# ThermoStat2.net
KiCad netlist of a schematic drawn in EAGLE
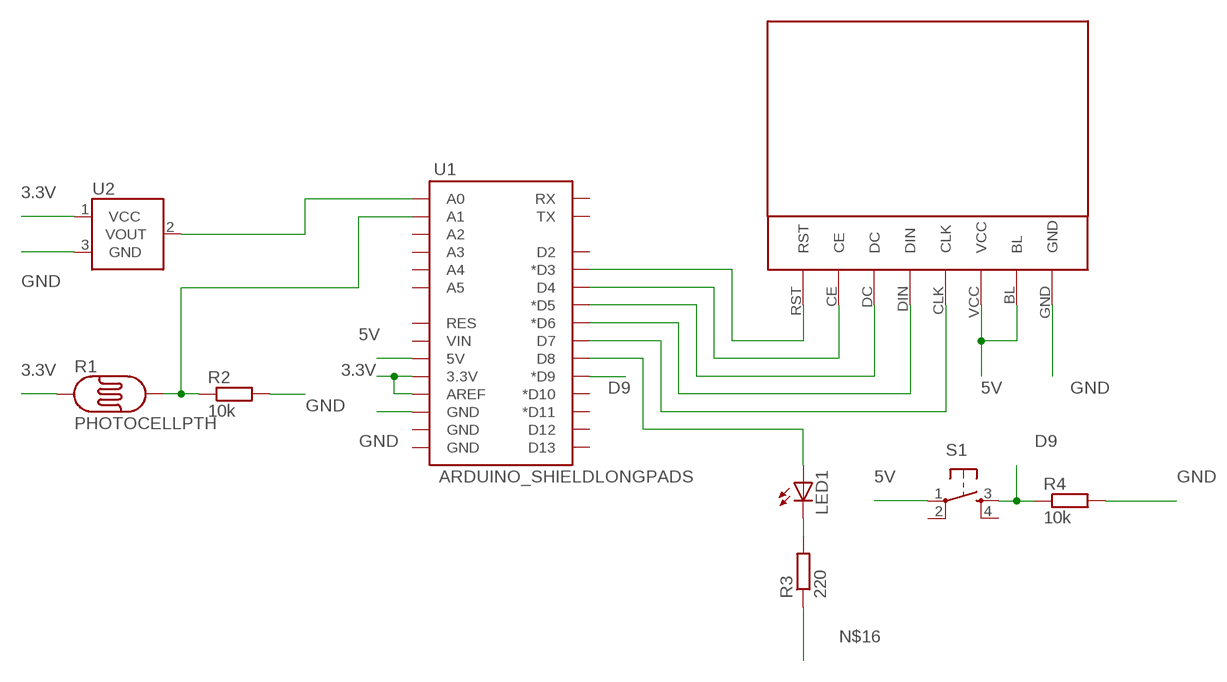
[diagram p0: schematic, sheet 1]

(export (version "E")
  (design (tool "Eeschema 10.0.6"))
  (components
    (comp (ref "LED1")
      (value "LED5MM")
      (footprint "eagle-import:LED5MM")
      (libsource (lib "eagle-import") (part "LED5MM"))
    )
    (comp (ref "R1")
      (value "PHOTOCELLPTH")
      (footprint "eagle-import:PHOTOCELL")
      (libsource (lib "eagle-import") (part "PHOTOCELLPTH"))
    )
    (comp (ref "R2")
      (value "10k")
      (footprint "eagle-import:0207_15")
      (libsource (lib "eagle-import") (part "R-EU_0207/15"))
    )
    (comp (ref "R3")
      (value "220")
      (footprint "eagle-import:0207_15")
      (libsource (lib "eagle-import") (part "R-EU_0207/15"))
    )
    (comp (ref "R4")
      (value "10k")
      (footprint "eagle-import:0207_15")
      (libsource (lib "eagle-import") (part "R-EU_0207/15"))
    )
    (comp (ref "S1")
      (value "TAC_SWITCHPTH")
      (footprint "eagle-import:TACTILE-PTH")
      (libsource (lib "eagle-import") (part "TAC_SWITCHPTH"))
    )
    (comp (ref "U$1")
      (value "NOKIA5510")
      (footprint "eagle-import:NOKIA5510")
      (libsource (lib "eagle-import") (part "NOKIA5510"))
    )
    (comp (ref "U1")
      (value "ARDUINO_SHIELDLONGPADS")
      (footprint "eagle-import:DUEMILANOVE_SHIELD_LONGPADS")
      (libsource (lib "eagle-import") (part "ARDUINO_SHIELDLONGPADS"))
    )
    (comp (ref "U2")
      (value "TMP36GT9")
      (footprint "eagle-import:TO-92")
      (libsource (lib "eagle-import") (part "TMP36GT9"))
    )
  )
  (nets
    (net (code "1") (name "/3.3V") (class "Default")
      (node (ref "R1") (pin "1") (pinfunction "P$1_1") (pintype "bidirectional"))
      (node (ref "U1") (pin "3.3V") (pinfunction "3.3V_3.3V") (pintype "bidirectional"))
      (node (ref "U1") (pin "AREF") (pinfunction "AREF_AREF") (pintype "bidirectional"))
      (node (ref "U2") (pin "1") (pinfunction "VCC_1") (pintype "bidirectional"))
    )
    (net (code "2") (name "/5V") (class "Default")
      (node (ref "S1") (pin "1") (pinfunction "1_1") (pintype "passive"))
      (node (ref "U$1") (pin "BL") (pinfunction "BL_BL") (pintype "bidirectional"))
      (node (ref "U$1") (pin "VCC") (pinfunction "VCC_VCC") (pintype "bidirectional"))
      (node (ref "U1") (pin "5V") (pinfunction "5V_5V") (pintype "bidirectional"))
    )
    (net (code "3") (name "/D9") (class "Default")
      (node (ref "R4") (pin "1") (pinfunction "1_1") (pintype "passive"))
      (node (ref "S1") (pin "3") (pinfunction "3_3") (pintype "passive"))
      (node (ref "U1") (pin "D9") (pinfunction "*D9_D9") (pintype "bidirectional"))
    )
    (net (code "4") (name "/GND") (class "Default")
      (node (ref "R2") (pin "2") (pinfunction "2_2") (pintype "passive"))
      (node (ref "R4") (pin "2") (pinfunction "2_2") (pintype "passive"))
      (node (ref "U$1") (pin "GND") (pinfunction "GND_GND") (pintype "bidirectional"))
      (node (ref "U1") (pin "GND@2") (pinfunction "GND_GND@2") (pintype "bidirectional"))
      (node (ref "U2") (pin "3") (pinfunction "GND_3") (pintype "bidirectional"))
    )
    (net (code "5") (name "/N$16") (class "Default")
      (node (ref "R3") (pin "1") (pinfunction "1_1") (pintype "passive"))
    )
    (net (code "6") (name "Net-(LED1-C)") (class "Default")
      (node (ref "LED1") (pin "K") (pinfunction "C_K") (pintype "passive"))
      (node (ref "R3") (pin "2") (pinfunction "2_2") (pintype "passive"))
    )
    (net (code "7") (name "Net-(LED1-PadA)") (class "Default")
      (node (ref "LED1") (pin "A") (pinfunction "A_A") (pintype "passive"))
      (node (ref "U1") (pin "D8") (pinfunction "D8_D8") (pintype "bidirectional"))
    )
    (net (code "8") (name "Net-(R1-P$2)") (class "Default")
      (node (ref "R1") (pin "2") (pinfunction "P$2_2") (pintype "bidirectional"))
      (node (ref "R2") (pin "1") (pinfunction "1_1") (pintype "passive"))
      (node (ref "U1") (pin "A1") (pinfunction "A1_A1") (pintype "bidirectional"))
    )
    (net (code "9") (name "Net-(U$1-PadCE)") (class "Default")
      (node (ref "U$1") (pin "CE") (pinfunction "CE_CE") (pintype "bidirectional"))
      (node (ref "U1") (pin "D4") (pinfunction "D4_D4") (pintype "bidirectional"))
    )
    (net (code "10") (name "Net-(U$1-PadCLK)") (class "Default")
      (node (ref "U$1") (pin "CLK") (pinfunction "CLK_CLK") (pintype "bidirectional"))
      (node (ref "U1") (pin "D7") (pinfunction "D7_D7") (pintype "bidirectional"))
    )
    (net (code "11") (name "Net-(U1-*D3)") (class "Default")
      (node (ref "U$1") (pin "RST") (pinfunction "RST_RST") (pintype "bidirectional"))
      (node (ref "U1") (pin "D3") (pinfunction "*D3_D3") (pintype "bidirectional"))
    )
    (net (code "12") (name "Net-(U1-*D5)") (class "Default")
      (node (ref "U$1") (pin "DC") (pinfunction "DC_DC") (pintype "bidirectional"))
      (node (ref "U1") (pin "D5") (pinfunction "*D5_D5") (pintype "bidirectional"))
    )
    (net (code "13") (name "Net-(U1-*D6)") (class "Default")
      (node (ref "U$1") (pin "DIN") (pinfunction "DIN_DIN") (pintype "bidirectional"))
      (node (ref "U1") (pin "D6") (pinfunction "*D6_D6") (pintype "bidirectional"))
    )
    (net (code "14") (name "Net-(U2-VOUT)") (class "Default")
      (node (ref "U1") (pin "A0") (pinfunction "A0_A0") (pintype "bidirectional"))
      (node (ref "U2") (pin "2") (pinfunction "VOUT_2") (pintype "bidirectional"))
    )
    (net (code "15") (name "unconnected-(S1-Pad2)") (class "Default")
      (node (ref "S1") (pin "2") (pinfunction "2_2") (pintype "passive"))
    )
    (net (code "16") (name "unconnected-(S1-Pad4)") (class "Default")
      (node (ref "S1") (pin "4") (pinfunction "4_4") (pintype "passive"))
    )
    (net (code "17") (name "unconnected-(U1-*D10-PadD10)") (class "Default")
      (node (ref "U1") (pin "D10") (pinfunction "*D10_D10") (pintype "bidirectional"))
    )
    (net (code "18") (name "unconnected-(U1-*D11-PadD11)") (class "Default")
      (node (ref "U1") (pin "D11") (pinfunction "*D11_D11") (pintype "bidirectional"))
    )
    (net (code "19") (name "unconnected-(U1-GND-PadGND@0)") (class "Default")
      (node (ref "U1") (pin "GND@0") (pinfunction "GND_GND@0") (pintype "bidirectional"))
    )
    (net (code "20") (name "unconnected-(U1-GND-PadGND@1)") (class "Default")
      (node (ref "U1") (pin "GND@1") (pinfunction "GND_GND@1") (pintype "bidirectional"))
    )
    (net (code "21") (name "unconnected-(U1-PadA2)") (class "Default")
      (node (ref "U1") (pin "A2") (pinfunction "A2_A2") (pintype "bidirectional"))
    )
    (net (code "22") (name "unconnected-(U1-PadA3)") (class "Default")
      (node (ref "U1") (pin "A3") (pinfunction "A3_A3") (pintype "bidirectional"))
    )
    (net (code "23") (name "unconnected-(U1-PadA4)") (class "Default")
      (node (ref "U1") (pin "A4") (pinfunction "A4_A4") (pintype "bidirectional"))
    )
    (net (code "24") (name "unconnected-(U1-PadA5)") (class "Default")
      (node (ref "U1") (pin "A5") (pinfunction "A5_A5") (pintype "bidirectional"))
    )
    (net (code "25") (name "unconnected-(U1-PadD2)") (class "Default")
      (node (ref "U1") (pin "D2") (pinfunction "D2_D2") (pintype "bidirectional"))
    )
    (net (code "26") (name "unconnected-(U1-PadD12)") (class "Default")
      (node (ref "U1") (pin "D12") (pinfunction "D12_D12") (pintype "bidirectional"))
    )
    (net (code "27") (name "unconnected-(U1-PadD13)") (class "Default")
      (node (ref "U1") (pin "D13") (pinfunction "D13_D13") (pintype "bidirectional"))
    )
    (net (code "28") (name "unconnected-(U1-PadRES)") (class "Default")
      (node (ref "U1") (pin "RES") (pinfunction "RES_RES") (pintype "bidirectional"))
    )
    (net (code "29") (name "unconnected-(U1-PadRX)") (class "Default")
      (node (ref "U1") (pin "RX") (pinfunction "RX_RX") (pintype "bidirectional"))
    )
    (net (code "30") (name "unconnected-(U1-PadTX)") (class "Default")
      (node (ref "U1") (pin "TX") (pinfunction "TX_TX") (pintype "bidirectional"))
    )
    (net (code "31") (name "unconnected-(U1-PadVIN)") (class "Default")
      (node (ref "U1") (pin "VIN") (pinfunction "VIN_VIN") (pintype "bidirectional"))
    )
  )
)
